# ksz8999-evm-dip-replacement.net
KiCad netlist of a schematic drawn in EAGLE
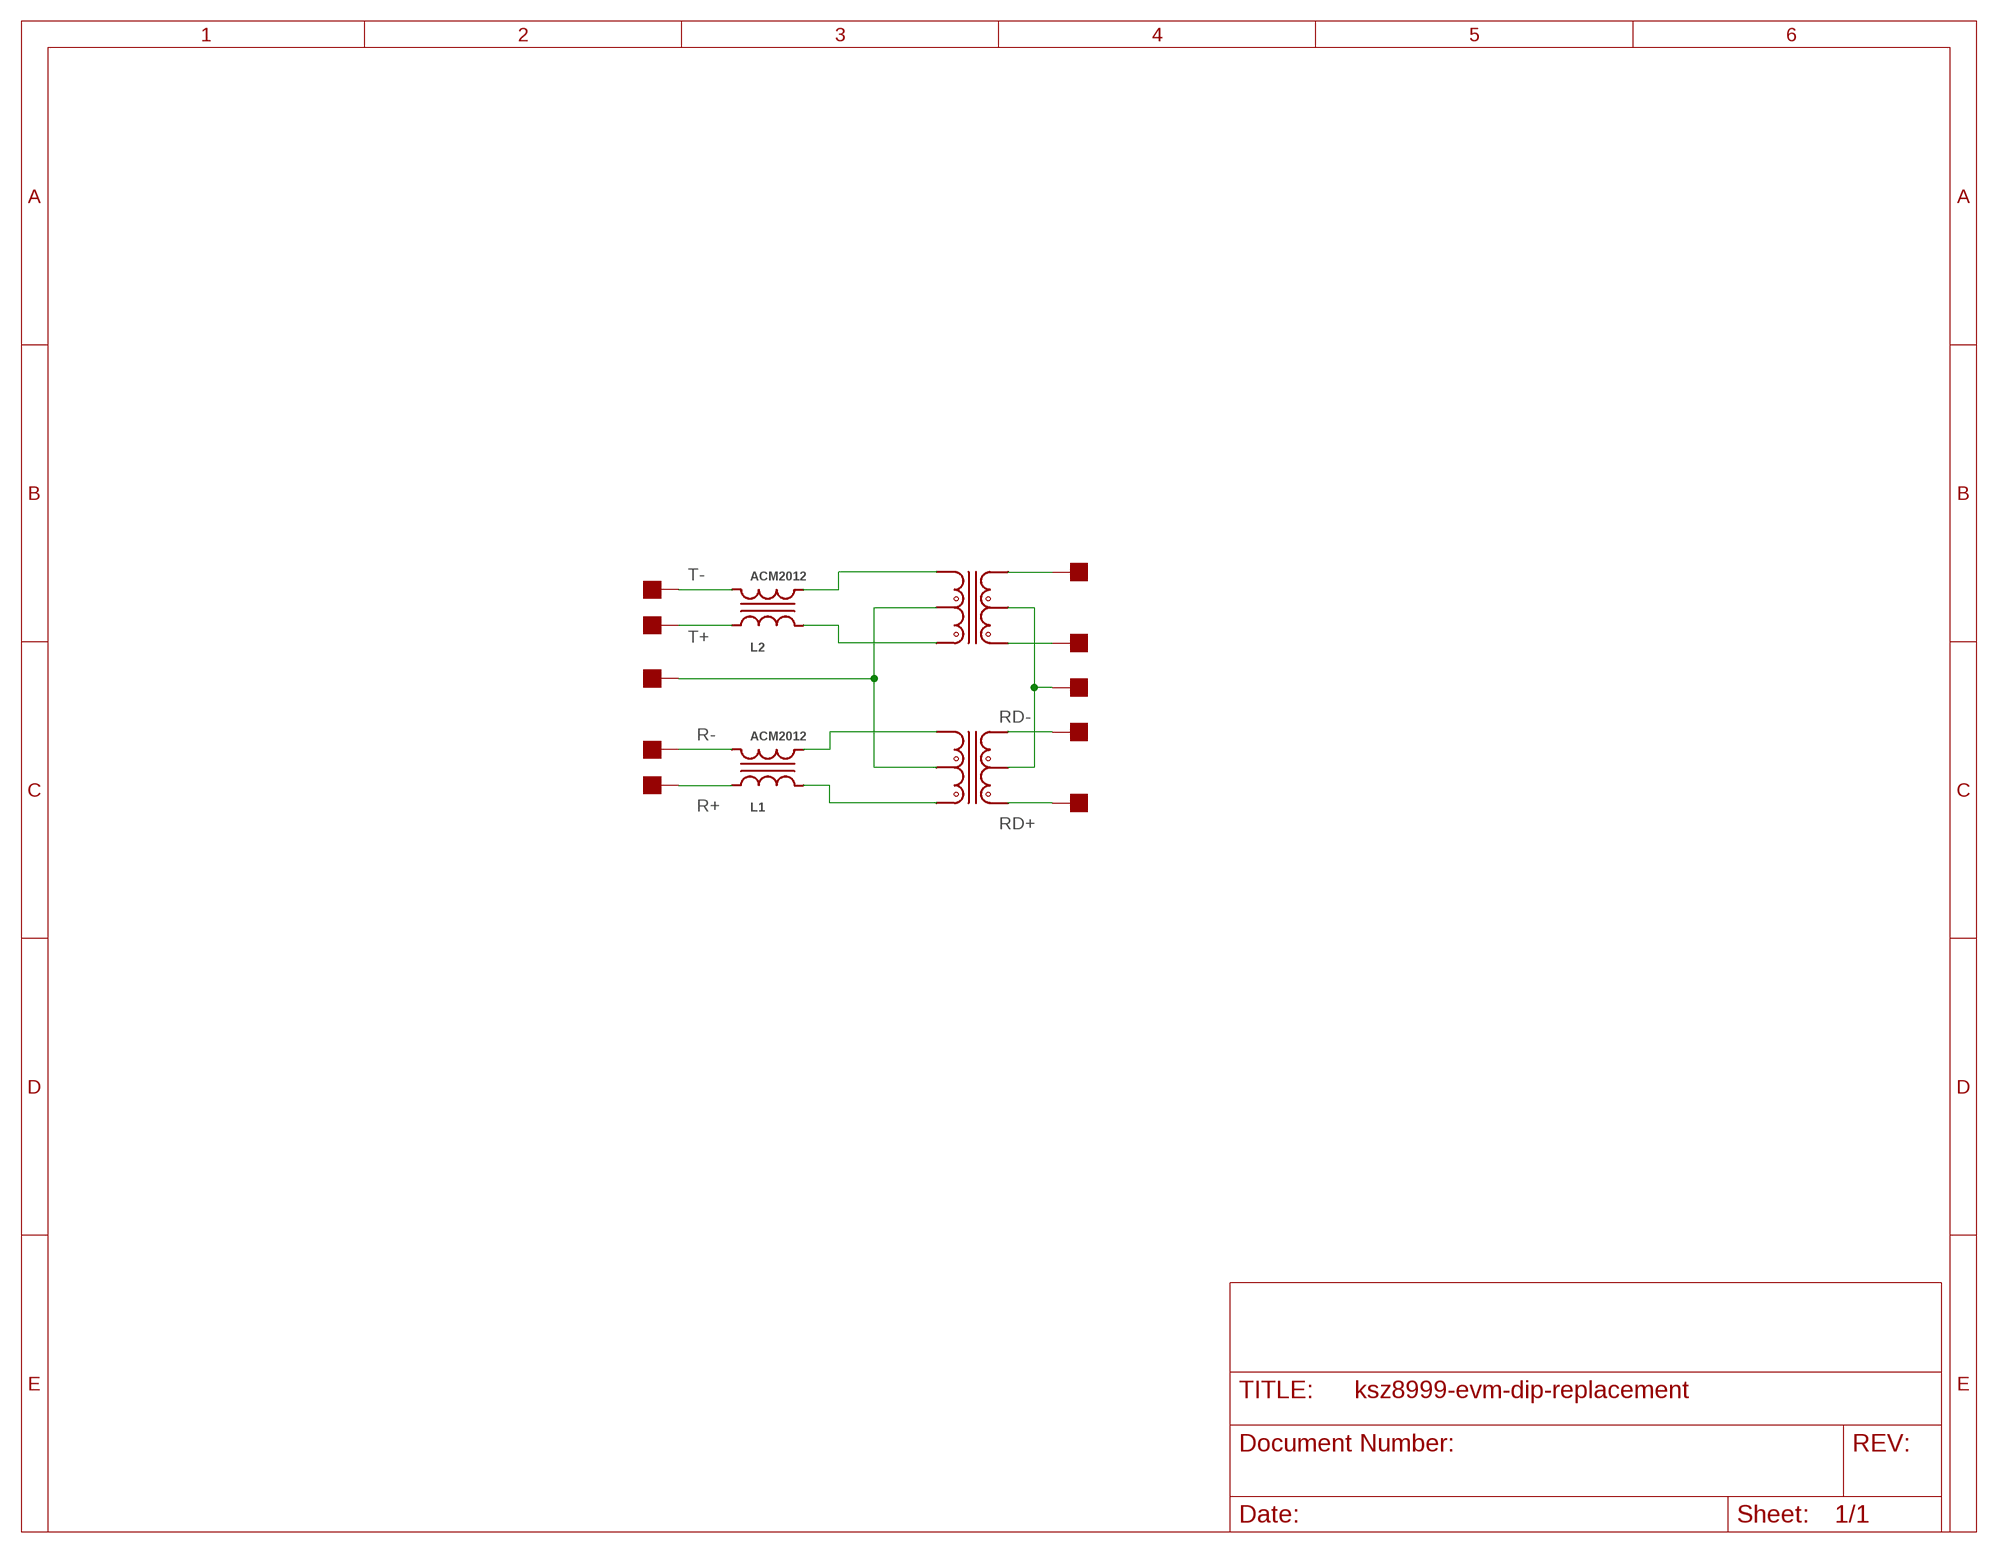
[diagram p0: schematic, sheet 1]

(export (version "E")
  (design (tool "Eeschema 10.0.6"))
  (components
    (comp (ref "L1")
      (value "ACM2012")
      (footprint "eagle-import:TDK-ACM2012")
      (libsource (lib "eagle-import") (part "ACM2012"))
    )
    (comp (ref "L2")
      (value "ACM2012")
      (footprint "eagle-import:TDK-ACM2012")
      (libsource (lib "eagle-import") (part "ACM2012"))
    )
    (comp (ref "T1")
      (value "ALT4532")
      (footprint "eagle-import:TDK-ALT4532")
      (libsource (lib "eagle-import") (part "ALT4532"))
    )
    (comp (ref "T2")
      (value "ALT4532")
      (footprint "eagle-import:TDK-ALT4532")
      (libsource (lib "eagle-import") (part "ALT4532"))
    )
    (comp (ref "TP1")
      (value "TEST-PAD")
      (footprint "eagle-import:TEST-PAD")
      (libsource (lib "eagle-import") (part "TEST-PAD"))
    )
    (comp (ref "TP2")
      (value "TEST-PAD")
      (footprint "eagle-import:TEST-PAD")
      (libsource (lib "eagle-import") (part "TEST-PAD"))
    )
    (comp (ref "TP3")
      (value "TEST-PAD")
      (footprint "eagle-import:TEST-PAD")
      (libsource (lib "eagle-import") (part "TEST-PAD"))
    )
    (comp (ref "TP4")
      (value "TEST-PAD")
      (footprint "eagle-import:TEST-PAD")
      (libsource (lib "eagle-import") (part "TEST-PAD"))
    )
    (comp (ref "TP6")
      (value "TEST-PAD")
      (footprint "eagle-import:TEST-PAD")
      (libsource (lib "eagle-import") (part "TEST-PAD"))
    )
    (comp (ref "TP7")
      (value "TEST-PAD")
      (footprint "eagle-import:TEST-PAD")
      (libsource (lib "eagle-import") (part "TEST-PAD"))
    )
    (comp (ref "TP8")
      (value "TEST-PAD")
      (footprint "eagle-import:TEST-PAD")
      (libsource (lib "eagle-import") (part "TEST-PAD"))
    )
    (comp (ref "TP9")
      (value "TEST-PAD")
      (footprint "eagle-import:TEST-PAD")
      (libsource (lib "eagle-import") (part "TEST-PAD"))
    )
    (comp (ref "TP10")
      (value "TEST-PAD")
      (footprint "eagle-import:TEST-PAD")
      (libsource (lib "eagle-import") (part "TEST-PAD"))
    )
    (comp (ref "TP11")
      (value "TEST-PAD")
      (footprint "eagle-import:TEST-PAD")
      (libsource (lib "eagle-import") (part "TEST-PAD"))
    )
  )
  (nets
    (net (code "1") (name "Net-(L1-Pad1)") (class "Default")
      (node (ref "L1") (pin "1") (pinfunction "1_1") (pintype "passive"))
      (node (ref "TP11") (pin "P$1") (pinfunction "P$1_P$1") (pintype "passive"))
    )
    (net (code "2") (name "Net-(L1-Pad2)") (class "Default")
      (node (ref "L1") (pin "2") (pinfunction "2_2") (pintype "passive"))
      (node (ref "TP10") (pin "P$1") (pinfunction "P$1_P$1") (pintype "passive"))
    )
    (net (code "3") (name "Net-(L1-Pad3)") (class "Default")
      (node (ref "L1") (pin "3") (pinfunction "3_3") (pintype "passive"))
      (node (ref "T1") (pin "4") (pinfunction "4_4") (pintype "passive"))
    )
    (net (code "4") (name "Net-(L1-Pad4)") (class "Default")
      (node (ref "L1") (pin "4") (pinfunction "4_4") (pintype "passive"))
      (node (ref "T1") (pin "5") (pinfunction "5_5") (pintype "passive"))
    )
    (net (code "5") (name "Net-(L2-Pad1)") (class "Default")
      (node (ref "L2") (pin "1") (pinfunction "1_1") (pintype "passive"))
      (node (ref "TP8") (pin "P$1") (pinfunction "P$1_P$1") (pintype "passive"))
    )
    (net (code "6") (name "Net-(L2-Pad2)") (class "Default")
      (node (ref "L2") (pin "2") (pinfunction "2_2") (pintype "passive"))
      (node (ref "TP7") (pin "P$1") (pinfunction "P$1_P$1") (pintype "passive"))
    )
    (net (code "7") (name "Net-(L2-Pad3)") (class "Default")
      (node (ref "L2") (pin "3") (pinfunction "3_3") (pintype "passive"))
      (node (ref "T2") (pin "4") (pinfunction "4_4") (pintype "passive"))
    )
    (net (code "8") (name "Net-(L2-Pad4)") (class "Default")
      (node (ref "L2") (pin "4") (pinfunction "4_4") (pintype "passive"))
      (node (ref "T2") (pin "5") (pinfunction "5_5") (pintype "passive"))
    )
    (net (code "9") (name "Net-(T1-Pad1)") (class "Default")
      (node (ref "T1") (pin "1") (pinfunction "1_1") (pintype "passive"))
      (node (ref "TP6") (pin "P$1") (pinfunction "P$1_P$1") (pintype "passive"))
    )
    (net (code "10") (name "Net-(T1-Pad2)") (class "Default")
      (node (ref "T1") (pin "2") (pinfunction "2_2") (pintype "passive"))
      (node (ref "TP4") (pin "P$1") (pinfunction "P$1_P$1") (pintype "passive"))
    )
    (net (code "11") (name "Net-(T1-Pad3)") (class "Default")
      (node (ref "T1") (pin "3") (pinfunction "3_3") (pintype "passive"))
      (node (ref "T2") (pin "3") (pinfunction "3_3") (pintype "passive"))
      (node (ref "TP9") (pin "P$1") (pinfunction "P$1_P$1") (pintype "passive"))
    )
    (net (code "12") (name "Net-(T1-Pad6)") (class "Default")
      (node (ref "T1") (pin "6") (pinfunction "6_6") (pintype "passive"))
      (node (ref "T2") (pin "6") (pinfunction "6_6") (pintype "passive"))
      (node (ref "TP2") (pin "P$1") (pinfunction "P$1_P$1") (pintype "passive"))
    )
    (net (code "13") (name "Net-(T2-Pad1)") (class "Default")
      (node (ref "T2") (pin "1") (pinfunction "1_1") (pintype "passive"))
      (node (ref "TP3") (pin "P$1") (pinfunction "P$1_P$1") (pintype "passive"))
    )
    (net (code "14") (name "Net-(T2-Pad2)") (class "Default")
      (node (ref "T2") (pin "2") (pinfunction "2_2") (pintype "passive"))
      (node (ref "TP1") (pin "P$1") (pinfunction "P$1_P$1") (pintype "passive"))
    )
  )
)
